# Audio.net
KiCad netlist of a schematic drawn in Altium Designer
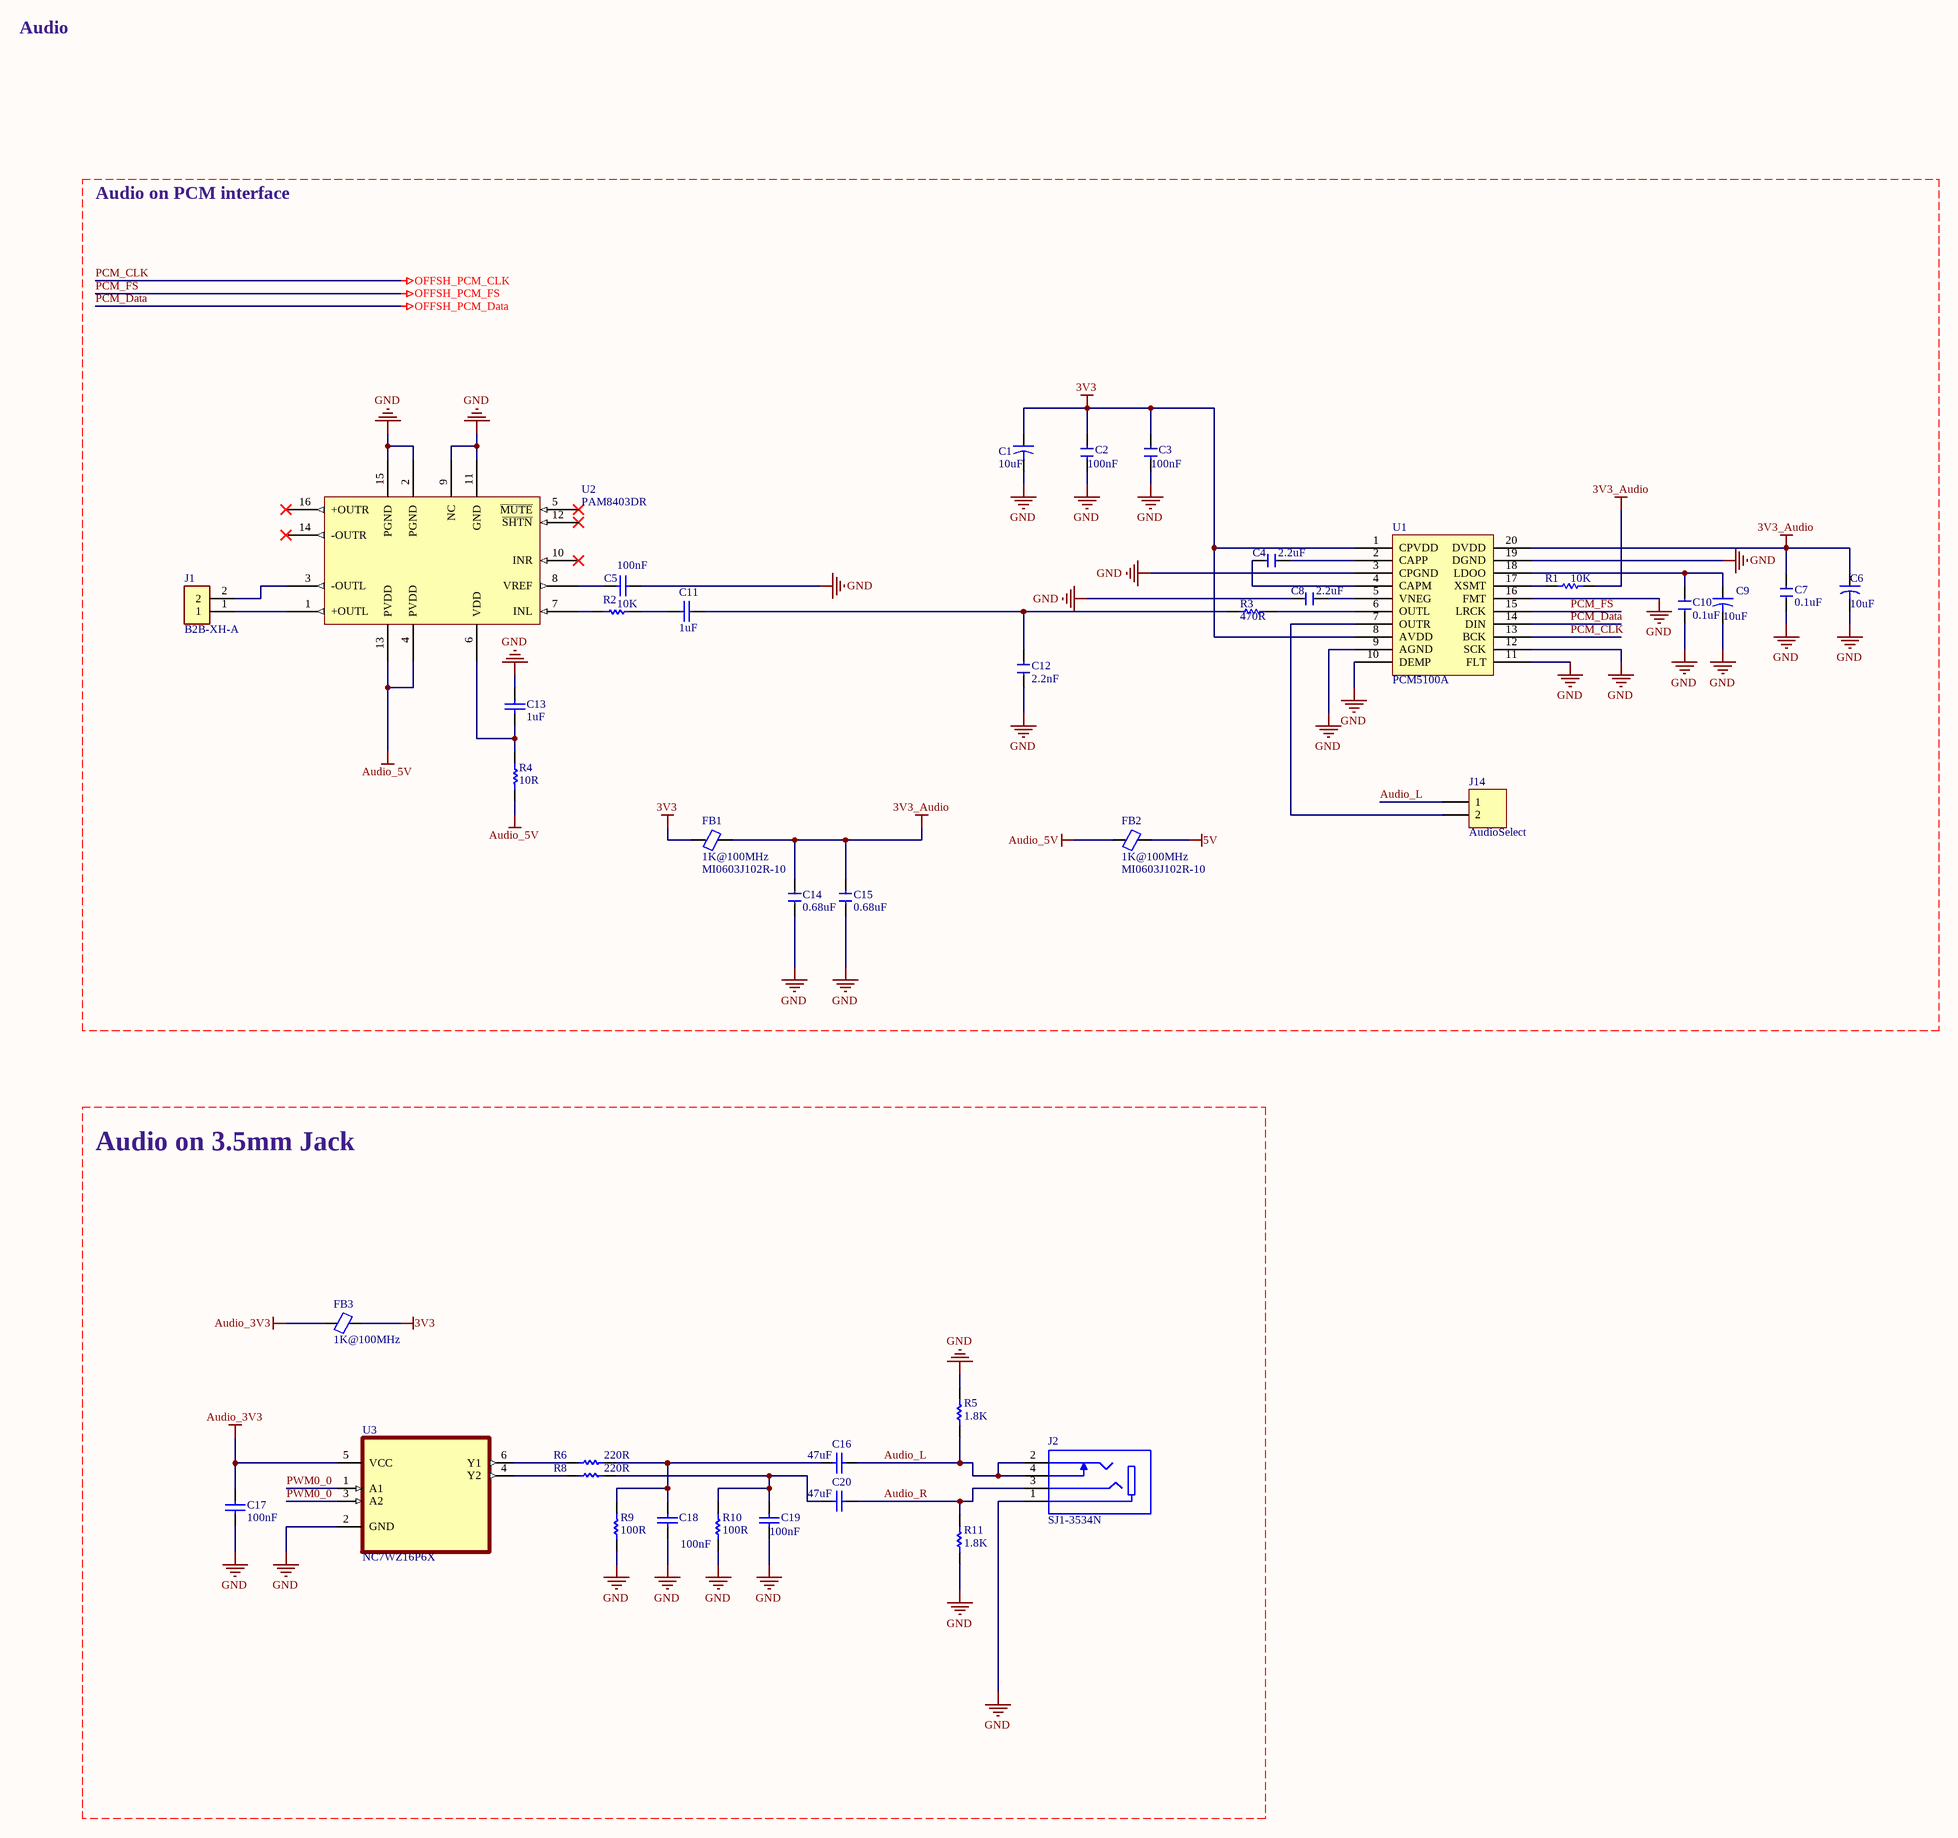
[diagram p0: Audio.SchDoc]

(export (version "E")
  (design (tool "Eeschema 10.0.6"))
  (components
    (comp (ref "C1")
      (value "10uF")
      (footprint "TANTAL (SIZE B)")
      (description "Tantalum Capacitor")
      (fields (field (name "VOLTAGE") "10V") (field (name "Comment") "Cap_Tantal"))
      (libsource (lib "SCSOFT_Utils") (part "Cap_Tantal"))
    )
    (comp (ref "C2")
      (value "100nF")
      (footprint "0603 Capacitor")
      (description "Ceramic Capacitor SMD")
      (fields (field (name "VOLTAGE") "10v") (field (name "TOLERANCE") "*%"))
      (libsource (lib "MaahMadarLib") (part "Capacitor Ceramic SMD"))
    )
    (comp (ref "C3")
      (value "100nF")
      (footprint "0603 Capacitor")
      (description "Ceramic Capacitor SMD")
      (fields (field (name "VOLTAGE") "10v") (field (name "TOLERANCE") "*%"))
      (libsource (lib "MaahMadarLib") (part "Capacitor Ceramic SMD"))
    )
    (comp (ref "C4")
      (value "2.2uF")
      (footprint "0603 Capacitor")
      (description "Ceramic Capacitor SMD")
      (fields (field (name "VOLTAGE") "10v") (field (name "TOLERANCE") "*%"))
      (libsource (lib "MaahMadarLib") (part "Capacitor Ceramic SMD"))
    )
    (comp (ref "C5")
      (value "100nF")
      (footprint "CAP (0603)")
      (description "SMD capacitor")
      (fields (field (name "VOLTAGE") "50V") (field (name "PART NUMBER") "SMD CAP (0603)"))
      (libsource (lib "*") (part "Cap"))
    )
    (comp (ref "C6")
      (value "10uF")
      (footprint "TANTAL (SIZE B)")
      (description "Tantalum Capacitor")
      (fields (field (name "VOLTAGE") "10V") (field (name "PART NUMBER") "Tantal"))
      (libsource (lib "SCSOFT_Utils") (part "Cap_Tantal"))
    )
    (comp (ref "C7")
      (value "0.1uF")
      (footprint "0603 Capacitor")
      (description "Ceramic Capacitor SMD")
      (fields (field (name "VOLTAGE") "10v") (field (name "TOLERANCE") "*%"))
      (libsource (lib "MaahMadarLib") (part "Capacitor Ceramic SMD"))
    )
    (comp (ref "C8")
      (value "2.2uF")
      (footprint "0603 Capacitor")
      (description "Ceramic Capacitor SMD")
      (fields (field (name "VOLTAGE") "10v") (field (name "TOLERANCE") "*%"))
      (libsource (lib "MaahMadarLib") (part "Capacitor Ceramic SMD"))
    )
    (comp (ref "C9")
      (value "10uF")
      (footprint "TANTAL (SIZE B)")
      (description "Tantalum Capacitor")
      (fields (field (name "VOLTAGE") "10V") (field (name "PART NUMBER") "Cap_Tantal"))
      (libsource (lib "SCSOFT_Utils") (part "Cap_Tantal"))
    )
    (comp (ref "C10")
      (value "0.1uF")
      (footprint "0603 Capacitor")
      (description "Ceramic Capacitor SMD")
      (fields (field (name "VOLTAGE") "10v") (field (name "TOLERANCE") "*%"))
      (libsource (lib "MaahMadarLib") (part "Capacitor Ceramic SMD"))
    )
    (comp (ref "C11")
      (value "1uF")
      (footprint "CAP (0603)")
      (description "SMD capacitor")
      (fields (field (name "VOLTAGE") "50V") (field (name "PART NUMBER") "SMD CAP (0603)"))
      (libsource (lib "*") (part "Cap"))
    )
    (comp (ref "C12")
      (value "2.2nF")
      (footprint "0603 Capacitor")
      (description "Ceramic Capacitor SMD")
      (fields (field (name "VOLTAGE") "10v") (field (name "TOLERANCE") "*%"))
      (libsource (lib "MaahMadarLib") (part "Capacitor Ceramic SMD"))
    )
    (comp (ref "C13")
      (value "1uF")
      (footprint "CAP (0603)")
      (description "SMD capacitor")
      (fields (field (name "VOLTAGE") "50V") (field (name "PART NUMBER") "SMD CAP (0603)"))
      (libsource (lib "*") (part "Cap"))
    )
    (comp (ref "C14")
      (value "0.68uF")
      (footprint "0603 Capacitor")
      (fields (field (name "VOLTAGE") "50v") (field (name "Comment") "Capacitor SMD"))
      (libsource (lib "SA-C7_Apr09") (part "Capacitor SMD"))
    )
    (comp (ref "C15")
      (value "0.68uF")
      (footprint "0603 Capacitor")
      (fields (field (name "VOLTAGE") "50v") (field (name "Comment") "Capacitor SMD"))
      (libsource (lib "SA-C7_Apr09") (part "Capacitor SMD"))
    )
    (comp (ref "C16")
      (value "47uF")
      (footprint "CAP (0805)")
      (description "SMD capacitor")
      (fields (field (name "VOLTAGE") "50V") (field (name "Comment") "Cap"))
      (libsource (lib "SCSOFT_Utils") (part "Cap"))
    )
    (comp (ref "C17")
      (value "100nF")
      (footprint "CAP (0603)")
      (description "SMD capacitor")
      (fields (field (name "VOLTAGE") "50V") (field (name "PART NUMBER") "SMD CAP (0603)"))
      (libsource (lib "*") (part "Cap"))
    )
    (comp (ref "C18")
      (value "100nF")
      (footprint "CAP (0603)")
      (description "SMD capacitor")
      (fields (field (name "VOLTAGE") "50V") (field (name "PART NUMBER") "SMD CAP (0603)"))
      (libsource (lib "*") (part "Cap"))
    )
    (comp (ref "C19")
      (value "100nF")
      (footprint "CAP (0603)")
      (description "SMD capacitor")
      (fields (field (name "VOLTAGE") "50V") (field (name "PART NUMBER") "SMD CAP (0603)"))
      (libsource (lib "*") (part "Cap"))
    )
    (comp (ref "C20")
      (value "47uF")
      (footprint "CAP (0805)")
      (description "SMD capacitor")
      (fields (field (name "VOLTAGE") "50V") (field (name "Comment") "Cap"))
      (libsource (lib "SCSOFT_Utils") (part "Cap"))
    )
    (comp (ref "FB1")
      (value "1K@100MHz")
      (footprint "FB0603")
      (description "Ferrite Bead SMD")
      (fields (field (name "PART NUMBER") "MI0603J102R-10") (field (name "Comment") "Ferrite Bead"))
      (libsource (lib "*") (part "Ferrite Bead"))
    )
    (comp (ref "FB2")
      (value "1K@100MHz")
      (footprint "FB0603")
      (description "Ferrite Bead SMD")
      (fields (field (name "PART NUMBER") "MI0603J102R-10") (field (name "Comment") "Ferrite Bead"))
      (libsource (lib "*") (part "Ferrite Bead"))
    )
    (comp (ref "FB3")
      (value "Ferrite Bead")
      (footprint "FB0603")
      (description "Ferrite Bead SMD")
      (fields (field (name "MI0603J102R-10") "1K@100MHz"))
      (libsource (lib "*") (part "Ferrite Bead"))
    )
    (comp (ref "J1")
      (value "XH Connector")
      (footprint "B2B-XH-A")
      (description "Header Through Hole 2 position (2.50mm)")
      (fields (field (name "PART NUMBER") "B2B-XH-A"))
      (libsource (lib "*") (part "B2B-XH-A"))
    )
    (comp (ref "J2")
      (value "SJ1-3534N")
      (footprint "SJ1-3534N:CUI_SJ1-3534N")
      (fields (field (name "MF") "CUI Devices"))
      (libsource (lib "SJ1-3534N") (part "SJ1-3534N"))
    )
    (comp (ref "J14")
      (value "AudioSelect")
      (footprint "HDR1X2")
      (description "Header, 2-Pin")
      (fields (field (name "PUBLISHER") "Altium Limited"))
      (libsource (lib "Miscellaneous Connectors") (part "Header 2"))
    )
    (comp (ref "R1")
      (value "10K")
      (footprint "R0603")
      (description "Resistor")
      (fields (field (name "Comment") "Res") (field (name "PUBLISHER") "Altium Limited"))
      (libsource (lib "onooma") (part "Res"))
    )
    (comp (ref "R2")
      (value "10K")
      (footprint "RES (0603)")
      (description "SMD resistor")
      (fields (field (name "TOLERANCE") "5%") (field (name "Comment") "Res"))
      (libsource (lib "*") (part "Res"))
    )
    (comp (ref "R3")
      (value "470R")
      (footprint "R0603")
      (description "Resistor")
      (fields (field (name "PUBLISHER") "Altium Limited"))
      (libsource (lib "onooma") (part "Res"))
    )
    (comp (ref "R4")
      (value "10R")
      (footprint "RES (0603)")
      (description "SMD resistor")
      (fields (field (name "TOLERANCE") "5%") (field (name "Comment") "Res"))
      (libsource (lib "*") (part "Res"))
    )
    (comp (ref "R5")
      (value "1.8K")
      (footprint "RES (0603)")
      (description "SMD resistor")
      (fields (field (name "TOLERANCE") "5%") (field (name "Comment") "Res"))
      (libsource (lib "*") (part "Res"))
    )
    (comp (ref "R6")
      (value "220R")
      (footprint "RES (0603)")
      (description "SMD resistor")
      (fields (field (name "TOLERANCE") "5%") (field (name "Comment") "Res"))
      (libsource (lib "*") (part "Res"))
    )
    (comp (ref "R8")
      (value "220R")
      (footprint "RES (0603)")
      (description "SMD resistor")
      (fields (field (name "TOLERANCE") "5%") (field (name "Comment") "Res"))
      (libsource (lib "*") (part "Res"))
    )
    (comp (ref "R9")
      (value "100R")
      (footprint "RES (0603)")
      (description "SMD resistor")
      (fields (field (name "TOLERANCE") "5%") (field (name "Comment") "Res"))
      (libsource (lib "*") (part "Res"))
    )
    (comp (ref "R10")
      (value "100R")
      (footprint "RES (0603)")
      (description "SMD resistor")
      (fields (field (name "TOLERANCE") "5%") (field (name "Comment") "Res"))
      (libsource (lib "*") (part "Res"))
    )
    (comp (ref "R11")
      (value "1.8K")
      (footprint "RES (0603)")
      (description "SMD resistor")
      (fields (field (name "TOLERANCE") "5%") (field (name "Comment") "Res"))
      (libsource (lib "*") (part "Res"))
    )
    (comp (ref "U1")
      (value "PCM5100A")
      (footprint "SOP65P640X120-20N")
      (libsource (lib "PCM5100A") (part "PCM5100A"))
    )
    (comp (ref "U2")
      (value "Audio Amp")
      (footprint "SOIC127P605X175-16N (SOIC16)")
      (description "Stereo Audio Amp")
      (fields (field (name "PART NUMBER") "PAM8403DR"))
      (libsource (lib "*") (part "PAM8403DR"))
    )
    (comp (ref "U3")
      (value "NC7WZ16P6X")
      (footprint "SOT65P210X110-6N")
      (description "Buffer, Non-Inverting 2 Element 1 Bit per Element Push-Pull Output SC-88 _SC-70-6_")
      (fields (field (name "MF") "ON Semiconductor"))
      (libsource (lib "NC7WZ16P6X") (part "NC7WZ16P6X"))
    )
  )
  (nets
    (net (code "1") (name "/Audio_L") (class "Default")
      (node (ref "C16") (pin "1") (pinfunction "1_1") (pintype "passive"))
      (node (ref "J14") (pin "1") (pinfunction "1_1") (pintype "passive"))
      (node (ref "J2") (pin "2") (pinfunction "2_2") (pintype "passive"))
      (node (ref "J2") (pin "4") (pinfunction "4_4") (pintype "passive"))
      (node (ref "R5") (pin "1") (pinfunction "1_1") (pintype "passive"))
    )
    (net (code "2") (name "/Audio_R") (class "Default")
      (node (ref "C20") (pin "1") (pinfunction "1_1") (pintype "passive"))
      (node (ref "J2") (pin "3") (pinfunction "3_3") (pintype "passive"))
      (node (ref "R11") (pin "2") (pinfunction "2_2") (pintype "passive"))
    )
    (net (code "3") (name "/PWM0_0") (class "Default")
      (node (ref "U3") (pin "1") (pinfunction "A1_1") (pintype "input"))
      (node (ref "U3") (pin "3") (pinfunction "A2_3") (pintype "input"))
    )
    (net (code "4") (name "3V3") (class "Default")
      (node (ref "C1") (pin "1") (pinfunction "1_1") (pintype "passive"))
      (node (ref "C2") (pin "2") (pintype "passive"))
      (node (ref "C3") (pin "2") (pintype "passive"))
      (node (ref "FB1") (pin "1") (pinfunction "1_1") (pintype "passive"))
      (node (ref "FB3") (pin "2") (pinfunction "2_2") (pintype "passive"))
      (node (ref "U1") (pin "1") (pinfunction "CPVDD_1") (pintype "passive"))
      (node (ref "U1") (pin "8") (pinfunction "AVDD_8") (pintype "passive"))
    )
    (net (code "5") (name "3V3_Audio") (class "Default")
      (node (ref "C14") (pin "1") (pintype "passive"))
      (node (ref "C15") (pin "1") (pintype "passive"))
      (node (ref "C6") (pin "1") (pinfunction "1_1") (pintype "passive"))
      (node (ref "C7") (pin "2") (pintype "passive"))
      (node (ref "FB1") (pin "2") (pinfunction "2_2") (pintype "passive"))
      (node (ref "R1") (pin "1") (pinfunction "1_1") (pintype "passive"))
      (node (ref "U1") (pin "20") (pinfunction "DVDD_20") (pintype "passive"))
    )
    (net (code "6") (name "5V") (class "Default")
      (node (ref "FB2") (pin "2") (pinfunction "2_2") (pintype "passive"))
    )
    (net (code "7") (name "Audio_3V3") (class "Default")
      (node (ref "C17") (pin "1") (pinfunction "1_1") (pintype "passive"))
      (node (ref "FB3") (pin "1") (pinfunction "1_1") (pintype "passive"))
      (node (ref "U3") (pin "5") (pinfunction "VCC_5") (pintype "power_in"))
    )
    (net (code "8") (name "Audio_5V") (class "Default")
      (node (ref "FB2") (pin "1") (pinfunction "1_1") (pintype "passive"))
      (node (ref "R4") (pin "2") (pinfunction "2_2") (pintype "passive"))
      (node (ref "U2") (pin "13") (pinfunction "PVDD_13") (pintype "power_in"))
      (node (ref "U2") (pin "4") (pinfunction "PVDD_4") (pintype "power_in"))
    )
    (net (code "9") (name "GND") (class "Default")
      (node (ref "C1") (pin "2") (pinfunction "2_2") (pintype "passive"))
      (node (ref "C10") (pin "1") (pintype "passive"))
      (node (ref "C12") (pin "1") (pintype "passive"))
      (node (ref "C13") (pin "1") (pinfunction "1_1") (pintype "passive"))
      (node (ref "C14") (pin "2") (pintype "passive"))
      (node (ref "C15") (pin "2") (pintype "passive"))
      (node (ref "C17") (pin "2") (pinfunction "2_2") (pintype "passive"))
      (node (ref "C18") (pin "2") (pinfunction "2_2") (pintype "passive"))
      (node (ref "C19") (pin "2") (pinfunction "2_2") (pintype "passive"))
      (node (ref "C2") (pin "1") (pintype "passive"))
      (node (ref "C3") (pin "1") (pintype "passive"))
      (node (ref "C5") (pin "2") (pinfunction "2_2") (pintype "passive"))
      (node (ref "C6") (pin "2") (pinfunction "2_2") (pintype "passive"))
      (node (ref "C7") (pin "1") (pintype "passive"))
      (node (ref "C8") (pin "2") (pintype "passive"))
      (node (ref "C9") (pin "2") (pinfunction "2_2") (pintype "passive"))
      (node (ref "J2") (pin "1") (pinfunction "1_1") (pintype "passive"))
      (node (ref "R10") (pin "1") (pinfunction "1_1") (pintype "passive"))
      (node (ref "R11") (pin "1") (pinfunction "1_1") (pintype "passive"))
      (node (ref "R5") (pin "2") (pinfunction "2_2") (pintype "passive"))
      (node (ref "R9") (pin "1") (pinfunction "1_1") (pintype "passive"))
      (node (ref "U1") (pin "10") (pinfunction "DEMP_10") (pintype "passive"))
      (node (ref "U1") (pin "11") (pinfunction "FLT_11") (pintype "passive"))
      (node (ref "U1") (pin "12") (pinfunction "SCK_12") (pintype "passive"))
      (node (ref "U1") (pin "16") (pinfunction "FMT_16") (pintype "passive"))
      (node (ref "U1") (pin "19") (pinfunction "DGND_19") (pintype "passive"))
      (node (ref "U1") (pin "3") (pinfunction "CPGND_3") (pintype "passive"))
      (node (ref "U1") (pin "9") (pinfunction "AGND_9") (pintype "passive"))
      (node (ref "U2") (pin "11") (pinfunction "GND_11") (pintype "power_in"))
      (node (ref "U2") (pin "15") (pinfunction "PGND_15") (pintype "power_in"))
      (node (ref "U2") (pin "2") (pinfunction "PGND_2") (pintype "power_in"))
      (node (ref "U2") (pin "9") (pinfunction "NC_9") (pintype "power_in"))
      (node (ref "U3") (pin "2") (pinfunction "GND_2") (pintype "passive"))
    )
    (net (code "10") (name "Net-(C11-Pad1)") (class "Default")
      (node (ref "C11") (pin "1") (pinfunction "1_1") (pintype "passive"))
      (node (ref "R2") (pin "1") (pinfunction "1_1") (pintype "passive"))
    )
    (net (code "11") (name "Net-(C11-Pad2)") (class "Default")
      (node (ref "C11") (pin "2") (pinfunction "2_2") (pintype "passive"))
      (node (ref "C12") (pin "2") (pintype "passive"))
      (node (ref "R3") (pin "2") (pinfunction "2_2") (pintype "passive"))
    )
    (net (code "12") (name "Net-(C16-Pad2)") (class "Default")
      (node (ref "C16") (pin "2") (pinfunction "2_2") (pintype "passive"))
      (node (ref "C18") (pin "1") (pinfunction "1_1") (pintype "passive"))
      (node (ref "R6") (pin "2") (pinfunction "2_2") (pintype "passive"))
      (node (ref "R9") (pin "2") (pinfunction "2_2") (pintype "passive"))
    )
    (net (code "13") (name "Net-(C19-Pad1)") (class "Default")
      (node (ref "C19") (pin "1") (pinfunction "1_1") (pintype "passive"))
      (node (ref "C20") (pin "2") (pinfunction "2_2") (pintype "passive"))
      (node (ref "R10") (pin "2") (pinfunction "2_2") (pintype "passive"))
      (node (ref "R8") (pin "2") (pinfunction "2_2") (pintype "passive"))
    )
    (net (code "14") (name "Net-(U1-CAPM)") (class "Default")
      (node (ref "C4") (pin "2") (pintype "passive"))
      (node (ref "U1") (pin "4") (pinfunction "CAPM_4") (pintype "passive"))
    )
    (net (code "15") (name "Net-(U1-CAPP)") (class "Default")
      (node (ref "C4") (pin "1") (pintype "passive"))
      (node (ref "U1") (pin "2") (pinfunction "CAPP_2") (pintype "passive"))
    )
    (net (code "16") (name "Net-(U1-LDOO)") (class "Default")
      (node (ref "C10") (pin "2") (pintype "passive"))
      (node (ref "C9") (pin "1") (pinfunction "1_1") (pintype "passive"))
      (node (ref "U1") (pin "18") (pinfunction "LDOO_18") (pintype "passive"))
    )
    (net (code "17") (name "Net-(U1-OUTL)") (class "Default")
      (node (ref "R3") (pin "1") (pinfunction "1_1") (pintype "passive"))
      (node (ref "U1") (pin "6") (pinfunction "OUTL_6") (pintype "passive"))
    )
    (net (code "18") (name "Net-(U1-OUTR)") (class "Default")
      (node (ref "J14") (pin "2") (pinfunction "2_2") (pintype "passive"))
      (node (ref "U1") (pin "7") (pinfunction "OUTR_7") (pintype "passive"))
    )
    (net (code "19") (name "Net-(U1-VNEG)") (class "Default")
      (node (ref "C8") (pin "1") (pintype "passive"))
      (node (ref "U1") (pin "5") (pinfunction "VNEG_5") (pintype "passive"))
    )
    (net (code "20") (name "Net-(U1-XSMT)") (class "Default")
      (node (ref "R1") (pin "2") (pinfunction "2_2") (pintype "passive"))
      (node (ref "U1") (pin "17") (pinfunction "XSMT_17") (pintype "passive"))
    )
    (net (code "21") (name "Net-(U2-+OUTL)") (class "Default")
      (node (ref "J1") (pin "1") (pinfunction "1_1") (pintype "passive"))
      (node (ref "U2") (pin "1") (pinfunction "+OUTL_1") (pintype "output"))
    )
    (net (code "22") (name "Net-(U2--OUTL)") (class "Default")
      (node (ref "J1") (pin "2") (pinfunction "2_2") (pintype "passive"))
      (node (ref "U2") (pin "3") (pinfunction "-OUTL_3") (pintype "output"))
    )
    (net (code "23") (name "Net-(U2-INL)") (class "Default")
      (node (ref "R2") (pin "2") (pinfunction "2_2") (pintype "passive"))
      (node (ref "U2") (pin "7") (pinfunction "INL_7") (pintype "input"))
    )
    (net (code "24") (name "Net-(U2-VDD)") (class "Default")
      (node (ref "C13") (pin "2") (pinfunction "2_2") (pintype "passive"))
      (node (ref "R4") (pin "1") (pinfunction "1_1") (pintype "passive"))
      (node (ref "U2") (pin "6") (pinfunction "VDD_6") (pintype "power_in"))
    )
    (net (code "25") (name "Net-(U2-VREF)") (class "Default")
      (node (ref "C5") (pin "1") (pinfunction "1_1") (pintype "passive"))
      (node (ref "U2") (pin "8") (pinfunction "VREF_8") (pintype "output"))
    )
    (net (code "26") (name "Net-(U3-Y1)") (class "Default")
      (node (ref "R6") (pin "1") (pinfunction "1_1") (pintype "passive"))
      (node (ref "U3") (pin "6") (pinfunction "Y1_6") (pintype "output"))
    )
    (net (code "27") (name "Net-(U3-Y2)") (class "Default")
      (node (ref "R8") (pin "1") (pinfunction "1_1") (pintype "passive"))
      (node (ref "U3") (pin "4") (pinfunction "Y2_4") (pintype "output"))
    )
    (net (code "28") (name "OFFSH_PCM_CLK") (class "Default")
      (node (ref "U1") (pin "13") (pinfunction "BCK_13") (pintype "passive"))
    )
    (net (code "29") (name "OFFSH_PCM_Data") (class "Default")
      (node (ref "U1") (pin "14") (pinfunction "DIN_14") (pintype "passive"))
    )
    (net (code "30") (name "OFFSH_PCM_FS") (class "Default")
      (node (ref "U1") (pin "15") (pinfunction "LRCK_15") (pintype "passive"))
    )
    (net (code "31") (name "unconnected-(U2-+OUTR-Pad16)") (class "Default")
      (node (ref "U2") (pin "16") (pinfunction "+OUTR_16") (pintype "output+no_connect"))
    )
    (net (code "32") (name "unconnected-(U2--OUTR-Pad14)") (class "Default")
      (node (ref "U2") (pin "14") (pinfunction "-OUTR_14") (pintype "output+no_connect"))
    )
    (net (code "33") (name "unconnected-(U2-INR-Pad10)") (class "Default")
      (node (ref "U2") (pin "10") (pinfunction "INR_10") (pintype "input+no_connect"))
    )
    (net (code "34") (name "unconnected-(U2-~{MUTE}-Pad5)") (class "Default")
      (node (ref "U2") (pin "5") (pinfunction "~{MUTE}_5") (pintype "input+no_connect"))
    )
    (net (code "35") (name "unconnected-(U2-~{SHTN}-Pad12)") (class "Default")
      (node (ref "U2") (pin "12") (pinfunction "~{SHTN}_12") (pintype "input+no_connect"))
    )
  )
)
